# Mtx6BR.net
KiCad netlist of a schematic drawn in EAGLE
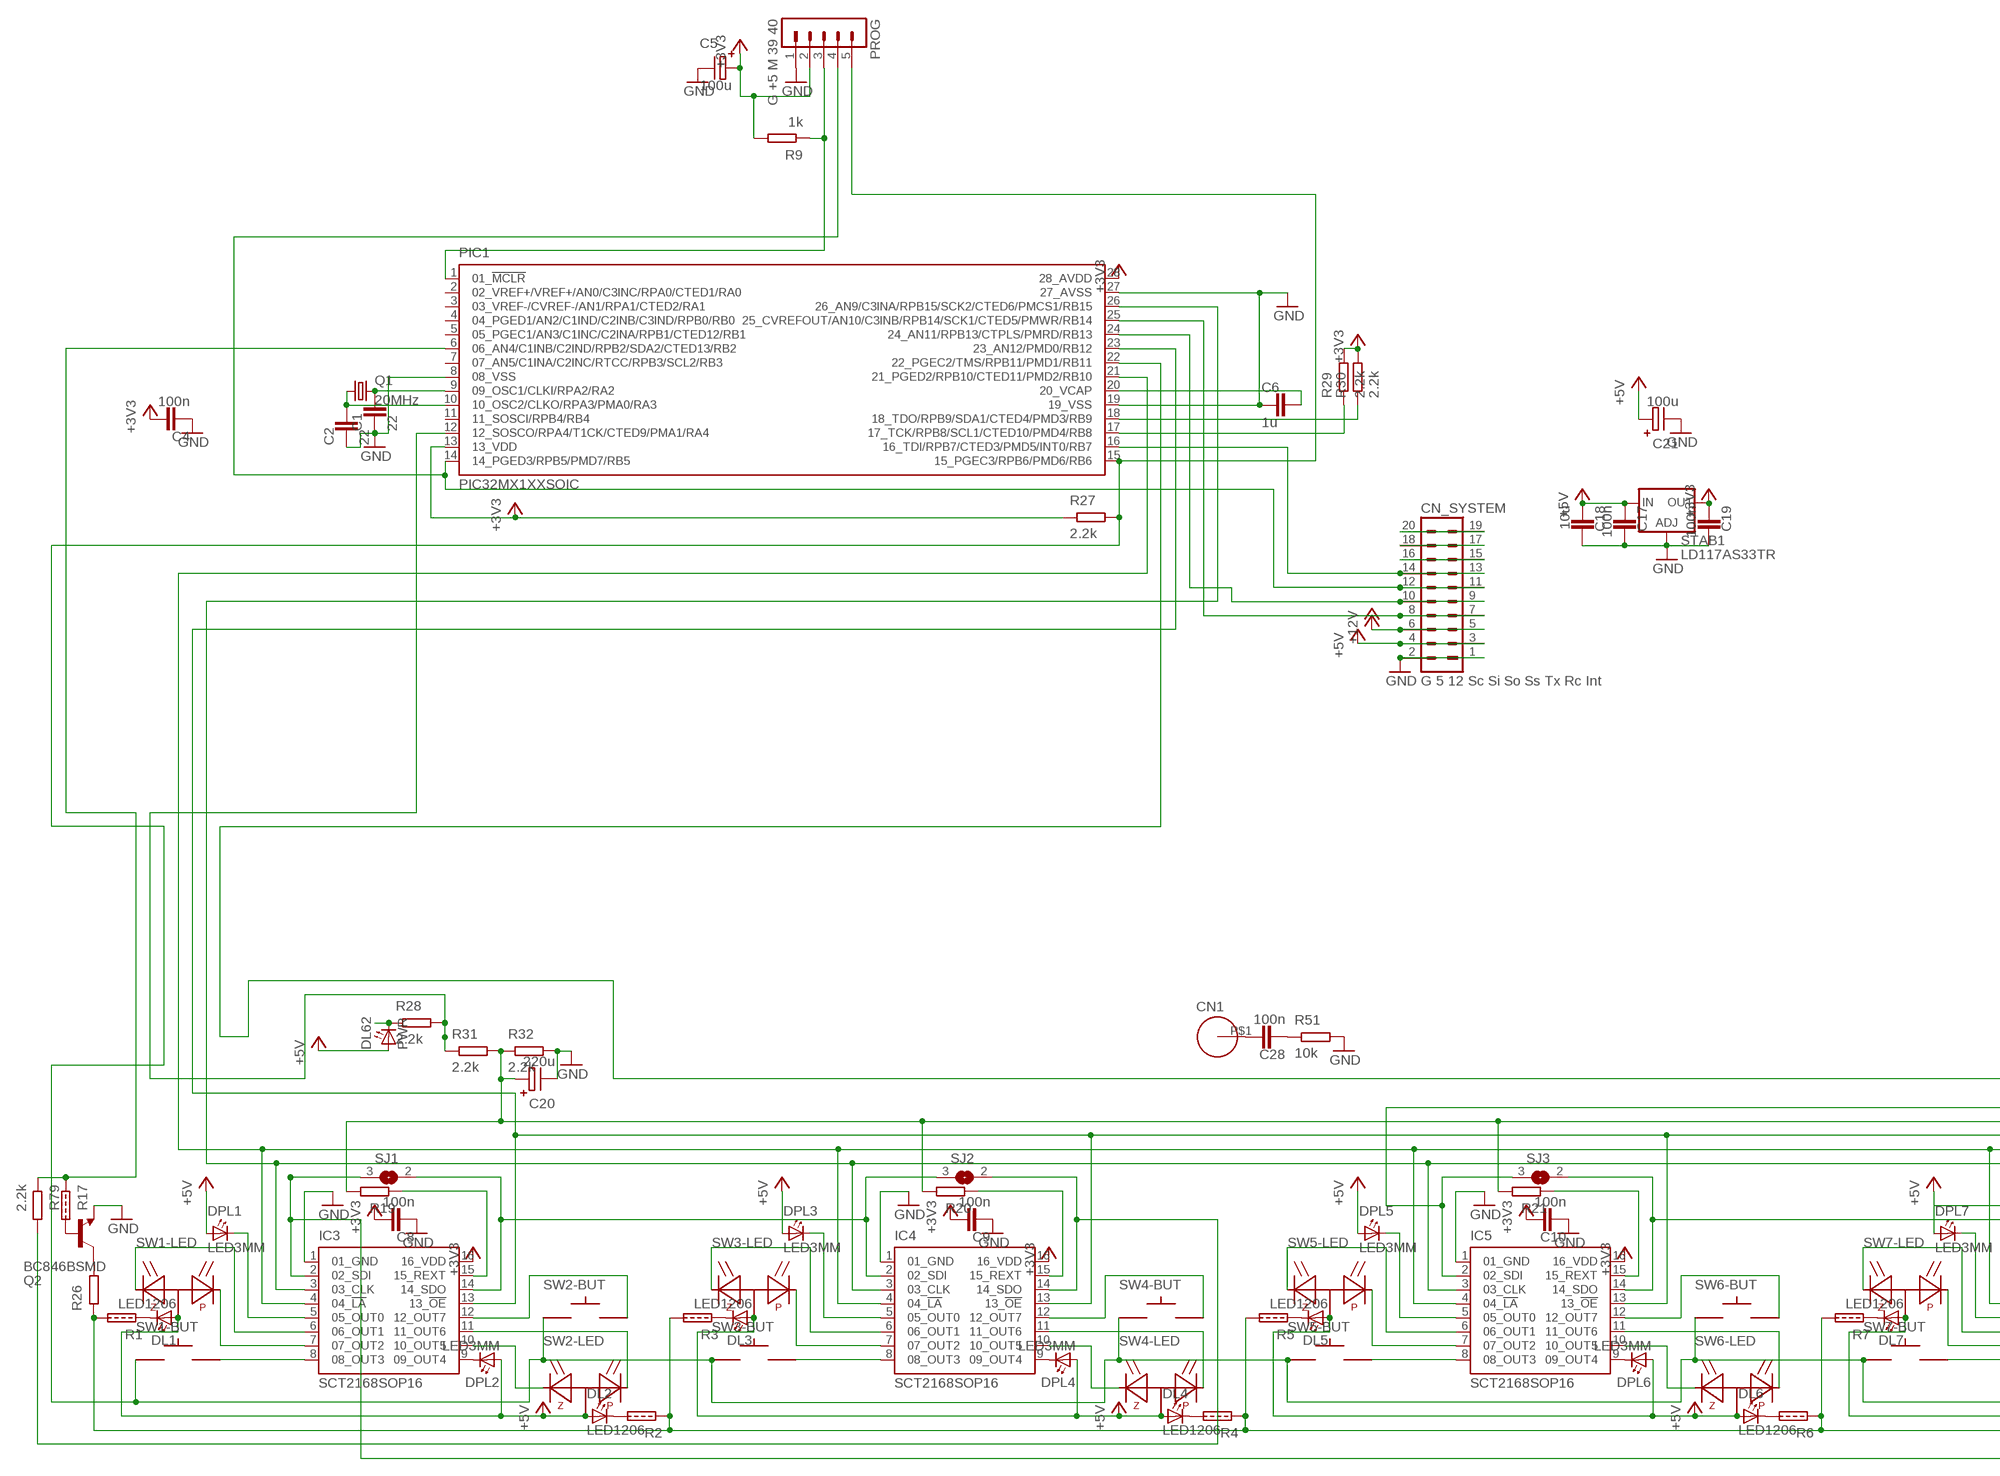
[diagram p0: schematic, sheet 1, part 1 of 2]
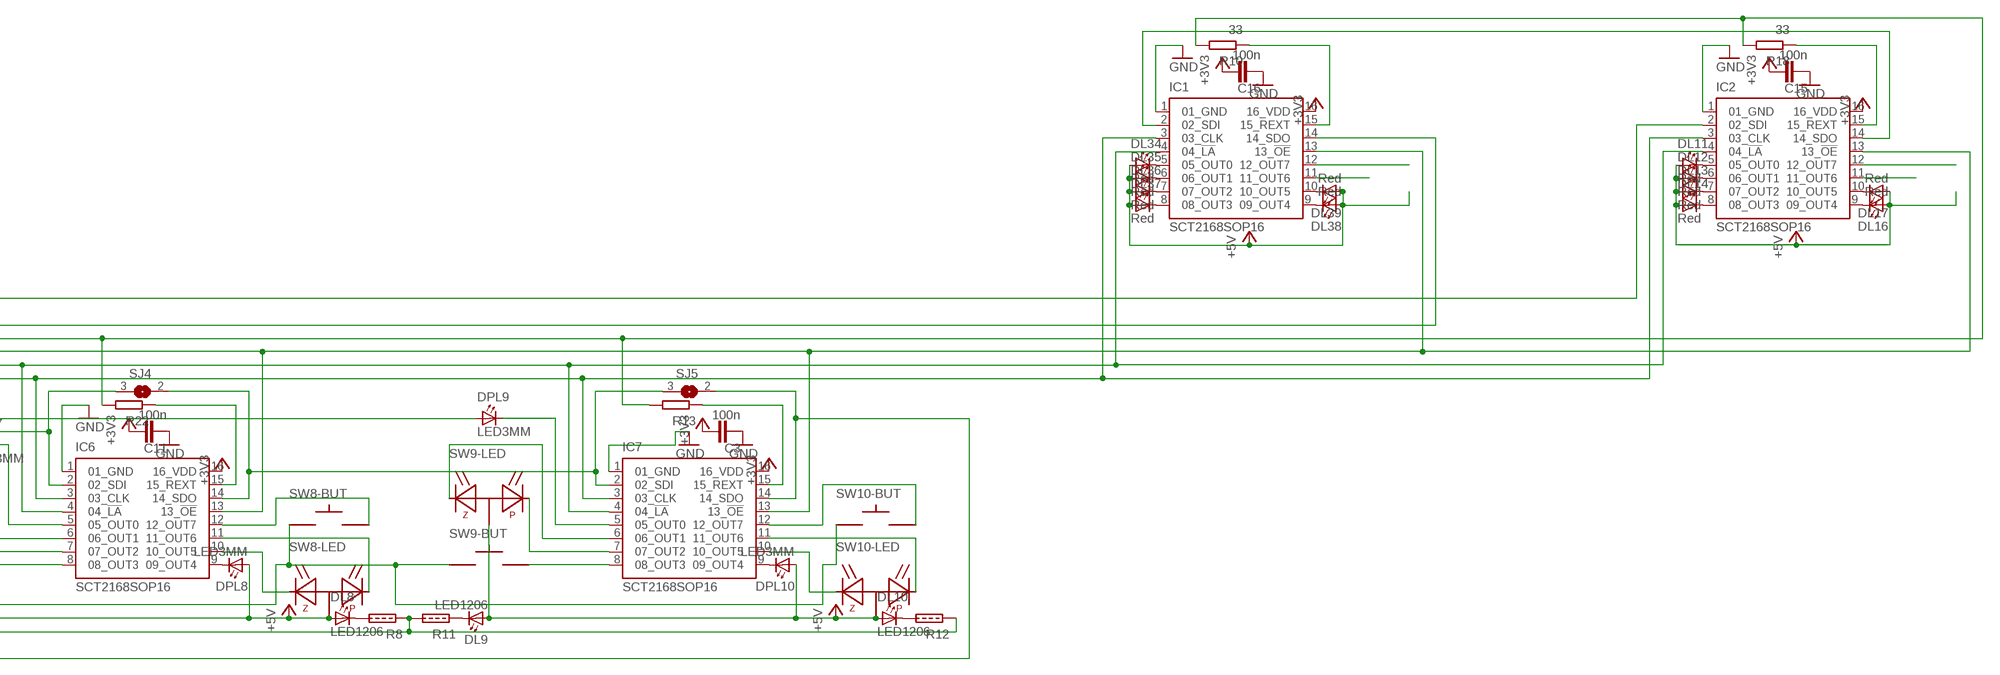
[diagram p1: schematic, sheet 1, part 2 of 2]

(export (version "E")
  (design (tool "Eeschema 10.0.6"))
  (components
    (comp (ref "C1")
      (value "22")
      (footprint "eagle-import:R0805")
      (libsource (lib "eagle-import") (part "C0805"))
    )
    (comp (ref "C2")
      (value "22")
      (footprint "eagle-import:R0805")
      (libsource (lib "eagle-import") (part "C0805"))
    )
    (comp (ref "C3")
      (value "100n")
      (footprint "eagle-import:R0805")
      (libsource (lib "eagle-import") (part "C0805"))
    )
    (comp (ref "C4")
      (value "100n")
      (footprint "eagle-import:R0805")
      (libsource (lib "eagle-import") (part "C0805"))
    )
    (comp (ref "C5")
      (value "100u")
      (footprint "eagle-import:C_EL1RASZT07")
      (libsource (lib "eagle-import") (part "C_EL1R07"))
    )
    (comp (ref "C6")
      (value "1u")
      (footprint "eagle-import:R0805")
      (libsource (lib "eagle-import") (part "C0805"))
    )
    (comp (ref "C8")
      (value "100n")
      (footprint "eagle-import:R0805")
      (libsource (lib "eagle-import") (part "C0805"))
    )
    (comp (ref "C9")
      (value "100n")
      (footprint "eagle-import:R0805")
      (libsource (lib "eagle-import") (part "C0805"))
    )
    (comp (ref "C10")
      (value "100n")
      (footprint "eagle-import:R0805")
      (libsource (lib "eagle-import") (part "C0805"))
    )
    (comp (ref "C11")
      (value "100n")
      (footprint "eagle-import:R0805")
      (libsource (lib "eagle-import") (part "C0805"))
    )
    (comp (ref "C15")
      (value "100n")
      (footprint "eagle-import:R0805")
      (libsource (lib "eagle-import") (part "C0805"))
    )
    (comp (ref "C16")
      (value "100n")
      (footprint "eagle-import:R0805")
      (libsource (lib "eagle-import") (part "C0805"))
    )
    (comp (ref "C17")
      (value "100n")
      (footprint "eagle-import:R0805")
      (libsource (lib "eagle-import") (part "C0805"))
    )
    (comp (ref "C18")
      (value "10u")
      (footprint "eagle-import:R0805")
      (libsource (lib "eagle-import") (part "C0805"))
    )
    (comp (ref "C19")
      (value "100n")
      (footprint "eagle-import:R0805")
      (libsource (lib "eagle-import") (part "C0805"))
    )
    (comp (ref "C20")
      (value "220u")
      (footprint "eagle-import:C_EL1RASZT07")
      (libsource (lib "eagle-import") (part "C_EL1R07"))
    )
    (comp (ref "C21")
      (value "100u")
      (footprint "eagle-import:C_EL1RASZT07")
      (libsource (lib "eagle-import") (part "C_EL1R07"))
    )
    (comp (ref "C28")
      (value "100n")
      (footprint "eagle-import:R0805")
      (libsource (lib "eagle-import") (part "C0805"))
    )
    (comp (ref "CN1")
      (value "TESTCSAVAR3.5")
      (footprint "eagle-import:TESTCSAVAR_3.5")
      (libsource (lib "eagle-import") (part "TESTCSAVAR3.5"))
    )
    (comp (ref "CN_SYSTEM")
      (value "G 5 12 Sc Si So Ss Tx Rc Int")
      (footprint "eagle-import:PIN10_2")
      (libsource (lib "eagle-import") (part "PIN10_2"))
    )
    (comp (ref "DL1")
      (value "LED1206")
      (footprint "eagle-import:R1206")
      (libsource (lib "eagle-import") (part "LED1206"))
    )
    (comp (ref "DL2")
      (value "LED1206")
      (footprint "eagle-import:R1206")
      (libsource (lib "eagle-import") (part "LED1206"))
    )
    (comp (ref "DL3")
      (value "LED1206")
      (footprint "eagle-import:R1206")
      (libsource (lib "eagle-import") (part "LED1206"))
    )
    (comp (ref "DL4")
      (value "LED1206")
      (footprint "eagle-import:R1206")
      (libsource (lib "eagle-import") (part "LED1206"))
    )
    (comp (ref "DL5")
      (value "LED1206")
      (footprint "eagle-import:R1206")
      (libsource (lib "eagle-import") (part "LED1206"))
    )
    (comp (ref "DL6")
      (value "LED1206")
      (footprint "eagle-import:R1206")
      (libsource (lib "eagle-import") (part "LED1206"))
    )
    (comp (ref "DL7")
      (value "LED1206")
      (footprint "eagle-import:R1206")
      (libsource (lib "eagle-import") (part "LED1206"))
    )
    (comp (ref "DL8")
      (value "LED1206")
      (footprint "eagle-import:R1206")
      (libsource (lib "eagle-import") (part "LED1206"))
    )
    (comp (ref "DL9")
      (value "LED1206")
      (footprint "eagle-import:R1206")
      (libsource (lib "eagle-import") (part "LED1206"))
    )
    (comp (ref "DL10")
      (value "LED1206")
      (footprint "eagle-import:R1206")
      (libsource (lib "eagle-import") (part "LED1206"))
    )
    (comp (ref "DL11")
      (value "Red")
      (footprint "eagle-import:LED5MM")
      (libsource (lib "eagle-import") (part "LED5MM"))
    )
    (comp (ref "DL12")
      (value "Red")
      (footprint "eagle-import:LED5MM")
      (libsource (lib "eagle-import") (part "LED5MM"))
    )
    (comp (ref "DL13")
      (value "Red")
      (footprint "eagle-import:LED5MM")
      (libsource (lib "eagle-import") (part "LED5MM"))
    )
    (comp (ref "DL14")
      (value "Red")
      (footprint "eagle-import:LED5MM")
      (libsource (lib "eagle-import") (part "LED5MM"))
    )
    (comp (ref "DL16")
      (value "Red")
      (footprint "eagle-import:LED5MM")
      (libsource (lib "eagle-import") (part "LED5MM"))
    )
    (comp (ref "DL17")
      (value "Red")
      (footprint "eagle-import:LED5MM")
      (libsource (lib "eagle-import") (part "LED5MM"))
    )
    (comp (ref "DL34")
      (value "Red")
      (footprint "eagle-import:LED5MM")
      (libsource (lib "eagle-import") (part "LED5MM"))
    )
    (comp (ref "DL35")
      (value "Red")
      (footprint "eagle-import:LED5MM")
      (libsource (lib "eagle-import") (part "LED5MM"))
    )
    (comp (ref "DL36")
      (value "Red")
      (footprint "eagle-import:LED5MM")
      (libsource (lib "eagle-import") (part "LED5MM"))
    )
    (comp (ref "DL37")
      (value "Red")
      (footprint "eagle-import:LED5MM")
      (libsource (lib "eagle-import") (part "LED5MM"))
    )
    (comp (ref "DL38")
      (value "Red")
      (footprint "eagle-import:LED5MM")
      (libsource (lib "eagle-import") (part "LED5MM"))
    )
    (comp (ref "DL39")
      (value "Red")
      (footprint "eagle-import:LED5MM")
      (libsource (lib "eagle-import") (part "LED5MM"))
    )
    (comp (ref "DL62")
      (value "PWR")
      (footprint "eagle-import:LED5MM")
      (libsource (lib "eagle-import") (part "LED5MM"))
    )
    (comp (ref "DPL1")
      (value "LED3MM")
      (footprint "eagle-import:LED3MM")
      (libsource (lib "eagle-import") (part "LED3MM"))
    )
    (comp (ref "DPL2")
      (value "LED3MM")
      (footprint "eagle-import:LED3MM")
      (libsource (lib "eagle-import") (part "LED3MM"))
    )
    (comp (ref "DPL3")
      (value "LED3MM")
      (footprint "eagle-import:LED3MM")
      (libsource (lib "eagle-import") (part "LED3MM"))
    )
    (comp (ref "DPL4")
      (value "LED3MM")
      (footprint "eagle-import:LED3MM")
      (libsource (lib "eagle-import") (part "LED3MM"))
    )
    (comp (ref "DPL5")
      (value "LED3MM")
      (footprint "eagle-import:LED3MM")
      (libsource (lib "eagle-import") (part "LED3MM"))
    )
    (comp (ref "DPL6")
      (value "LED3MM")
      (footprint "eagle-import:LED3MM")
      (libsource (lib "eagle-import") (part "LED3MM"))
    )
    (comp (ref "DPL7")
      (value "LED3MM")
      (footprint "eagle-import:LED3MM")
      (libsource (lib "eagle-import") (part "LED3MM"))
    )
    (comp (ref "DPL8")
      (value "LED3MM")
      (footprint "eagle-import:LED3MM")
      (libsource (lib "eagle-import") (part "LED3MM"))
    )
    (comp (ref "DPL9")
      (value "LED3MM")
      (footprint "eagle-import:LED3MM")
      (libsource (lib "eagle-import") (part "LED3MM"))
    )
    (comp (ref "DPL10")
      (value "LED3MM")
      (footprint "eagle-import:LED3MM")
      (libsource (lib "eagle-import") (part "LED3MM"))
    )
    (comp (ref "IC1")
      (value "SCT2168SOP16")
      (footprint "eagle-import:SO16")
      (libsource (lib "eagle-import") (part "SCT2168SOP16"))
    )
    (comp (ref "IC2")
      (value "SCT2168SOP16")
      (footprint "eagle-import:SO16")
      (libsource (lib "eagle-import") (part "SCT2168SOP16"))
    )
    (comp (ref "IC3")
      (value "SCT2168SOP16")
      (footprint "eagle-import:SO16")
      (libsource (lib "eagle-import") (part "SCT2168SOP16"))
    )
    (comp (ref "IC4")
      (value "SCT2168SOP16")
      (footprint "eagle-import:SO16")
      (libsource (lib "eagle-import") (part "SCT2168SOP16"))
    )
    (comp (ref "IC5")
      (value "SCT2168SOP16")
      (footprint "eagle-import:SO16")
      (libsource (lib "eagle-import") (part "SCT2168SOP16"))
    )
    (comp (ref "IC6")
      (value "SCT2168SOP16")
      (footprint "eagle-import:SO16")
      (libsource (lib "eagle-import") (part "SCT2168SOP16"))
    )
    (comp (ref "IC7")
      (value "SCT2168SOP16")
      (footprint "eagle-import:SO16")
      (libsource (lib "eagle-import") (part "SCT2168SOP16"))
    )
    (comp (ref "PIC1")
      (value "PIC32MX1XXSOIC")
      (footprint "eagle-import:SOIC127P1032X265-28N")
      (libsource (lib "eagle-import") (part "PIC32MX1XXSOIC"))
    )
    (comp (ref "PROG")
      (value "G +5 M 39 40")
      (footprint "eagle-import:PIN05_1")
      (libsource (lib "eagle-import") (part "PIN05_1"))
    )
    (comp (ref "Q1")
      (value "20MHz")
      (footprint "eagle-import:XTAL_NAGYSMD")
      (libsource (lib "eagle-import") (part "XTAL_2NAGYSMD"))
    )
    (comp (ref "Q2")
      (value "BC846BSMD")
      (footprint "eagle-import:SOT23")
      (libsource (lib "eagle-import") (part "BC846SMDB"))
    )
    (comp (ref "R1")
      (value "RNULL_EU0805")
      (footprint "eagle-import:R0805_C")
      (libsource (lib "eagle-import") (part "RNULL_EU0805"))
    )
    (comp (ref "R2")
      (value "RNULL_EU0805")
      (footprint "eagle-import:R0805_C")
      (libsource (lib "eagle-import") (part "RNULL_EU0805"))
    )
    (comp (ref "R3")
      (value "RNULL_EU0805")
      (footprint "eagle-import:R0805_C")
      (libsource (lib "eagle-import") (part "RNULL_EU0805"))
    )
    (comp (ref "R4")
      (value "RNULL_EU0805")
      (footprint "eagle-import:R0805_C")
      (libsource (lib "eagle-import") (part "RNULL_EU0805"))
    )
    (comp (ref "R5")
      (value "RNULL_EU0805")
      (footprint "eagle-import:R0805_C")
      (libsource (lib "eagle-import") (part "RNULL_EU0805"))
    )
    (comp (ref "R6")
      (value "RNULL_EU0805")
      (footprint "eagle-import:R0805_C")
      (libsource (lib "eagle-import") (part "RNULL_EU0805"))
    )
    (comp (ref "R7")
      (value "RNULL_EU0805")
      (footprint "eagle-import:R0805_C")
      (libsource (lib "eagle-import") (part "RNULL_EU0805"))
    )
    (comp (ref "R8")
      (value "RNULL_EU0805")
      (footprint "eagle-import:R0805_C")
      (libsource (lib "eagle-import") (part "RNULL_EU0805"))
    )
    (comp (ref "R9")
      (value "1k")
      (footprint "eagle-import:R0805")
      (libsource (lib "eagle-import") (part "R_EU0805"))
    )
    (comp (ref "R10")
      (value "33")
      (footprint "eagle-import:R0805")
      (libsource (lib "eagle-import") (part "R_EU0805"))
    )
    (comp (ref "R11")
      (value "RNULL_EU0805")
      (footprint "eagle-import:R0805_C")
      (libsource (lib "eagle-import") (part "RNULL_EU0805"))
    )
    (comp (ref "R12")
      (value "RNULL_EU0805")
      (footprint "eagle-import:R0805_C")
      (libsource (lib "eagle-import") (part "RNULL_EU0805"))
    )
    (comp (ref "R13")
      (value "R_EU0805")
      (footprint "eagle-import:R0805")
      (libsource (lib "eagle-import") (part "R_EU0805"))
    )
    (comp (ref "R17")
      (value "RNULL_EU0805")
      (footprint "eagle-import:R0805_C")
      (libsource (lib "eagle-import") (part "RNULL_EU0805"))
    )
    (comp (ref "R18")
      (value "33")
      (footprint "eagle-import:R0805")
      (libsource (lib "eagle-import") (part "R_EU0805"))
    )
    (comp (ref "R19")
      (value "R_EU0805")
      (footprint "eagle-import:R0805")
      (libsource (lib "eagle-import") (part "R_EU0805"))
    )
    (comp (ref "R20")
      (value "R_EU0805")
      (footprint "eagle-import:R0805")
      (libsource (lib "eagle-import") (part "R_EU0805"))
    )
    (comp (ref "R21")
      (value "R_EU0805")
      (footprint "eagle-import:R0805")
      (libsource (lib "eagle-import") (part "R_EU0805"))
    )
    (comp (ref "R22")
      (value "R_EU0805")
      (footprint "eagle-import:R0805")
      (libsource (lib "eagle-import") (part "R_EU0805"))
    )
    (comp (ref "R26")
      (value "R_EU0805")
      (footprint "eagle-import:R0805")
      (libsource (lib "eagle-import") (part "R_EU0805"))
    )
    (comp (ref "R27")
      (value "2.2k")
      (footprint "eagle-import:R0805")
      (libsource (lib "eagle-import") (part "R_EU0805"))
    )
    (comp (ref "R28")
      (value "2.2k")
      (footprint "eagle-import:R0805")
      (libsource (lib "eagle-import") (part "R_EU0805"))
    )
    (comp (ref "R29")
      (value "2.2k")
      (footprint "eagle-import:R0805")
      (libsource (lib "eagle-import") (part "R_EU0805"))
    )
    (comp (ref "R30")
      (value "2.2k")
      (footprint "eagle-import:R0805")
      (libsource (lib "eagle-import") (part "R_EU0805"))
    )
    (comp (ref "R31")
      (value "2.2k")
      (footprint "eagle-import:R0805")
      (libsource (lib "eagle-import") (part "R_EU0805"))
    )
    (comp (ref "R32")
      (value "2.2k")
      (footprint "eagle-import:R0805")
      (libsource (lib "eagle-import") (part "R_EU0805"))
    )
    (comp (ref "R51")
      (value "10k")
      (footprint "eagle-import:R0805")
      (libsource (lib "eagle-import") (part "R_EU0805"))
    )
    (comp (ref "R79")
      (value "2.2k")
      (footprint "eagle-import:R0805")
      (libsource (lib "eagle-import") (part "R_EU0805"))
    )
    (comp (ref "SJ1") (value "SJ") (footprint "eagle-import:SJ") (libsource (lib "eagle-import") (part "SJ")))
    (comp (ref "SJ2") (value "SJ") (footprint "eagle-import:SJ") (libsource (lib "eagle-import") (part "SJ")))
    (comp (ref "SJ3") (value "SJ") (footprint "eagle-import:SJ") (libsource (lib "eagle-import") (part "SJ")))
    (comp (ref "SJ4") (value "SJ") (footprint "eagle-import:SJ") (libsource (lib "eagle-import") (part "SJ")))
    (comp (ref "SJ5") (value "SJ") (footprint "eagle-import:SJ") (libsource (lib "eagle-import") (part "SJ")))
    (comp (ref "STAB1")
      (value "LD117AS33TR")
      (footprint "eagle-import:SOT223")
      (libsource (lib "eagle-import") (part "LD117A?S33TR"))
    )
    (comp (ref "SW1")
      (value "SPG2")
      (footprint "eagle-import:SPG2_3LED")
      (libsource (lib "eagle-import") (part "SPG2"))
    )
    (comp (ref "SW2")
      (value "SPG2")
      (footprint "eagle-import:SPG2_3LED")
      (libsource (lib "eagle-import") (part "SPG2"))
    )
    (comp (ref "SW3")
      (value "SPG2")
      (footprint "eagle-import:SPG2_3LED")
      (libsource (lib "eagle-import") (part "SPG2"))
    )
    (comp (ref "SW4")
      (value "SPG2")
      (footprint "eagle-import:SPG2_3LED")
      (libsource (lib "eagle-import") (part "SPG2"))
    )
    (comp (ref "SW5")
      (value "SPG2")
      (footprint "eagle-import:SPG2_3LED")
      (libsource (lib "eagle-import") (part "SPG2"))
    )
    (comp (ref "SW6")
      (value "SPG2")
      (footprint "eagle-import:SPG2_3LED")
      (libsource (lib "eagle-import") (part "SPG2"))
    )
    (comp (ref "SW7")
      (value "SPG2")
      (footprint "eagle-import:SPG2_3LED")
      (libsource (lib "eagle-import") (part "SPG2"))
    )
    (comp (ref "SW8")
      (value "SPG2")
      (footprint "eagle-import:SPG2_3LED")
      (libsource (lib "eagle-import") (part "SPG2"))
    )
    (comp (ref "SW9")
      (value "SPG2")
      (footprint "eagle-import:SPG2_3LED")
      (libsource (lib "eagle-import") (part "SPG2"))
    )
    (comp (ref "SW10")
      (value "SPG2")
      (footprint "eagle-import:SPG2_3LED")
      (libsource (lib "eagle-import") (part "SPG2"))
    )
  )
  (nets
    (net (code "1") (name "+3V3") (class "Default")
      (node (ref "C10") (pin "1") (pinfunction "1_1") (pintype "passive"))
      (node (ref "C11") (pin "1") (pinfunction "1_1") (pintype "passive"))
      (node (ref "C15") (pin "1") (pinfunction "1_1") (pintype "passive"))
      (node (ref "C16") (pin "1") (pinfunction "1_1") (pintype "passive"))
      (node (ref "C19") (pin "2") (pinfunction "2_2") (pintype "passive"))
      (node (ref "C3") (pin "1") (pinfunction "1_1") (pintype "passive"))
      (node (ref "C4") (pin "1") (pinfunction "1_1") (pintype "passive"))
      (node (ref "C5") (pin "P+") (pinfunction "P+_P+") (pintype "passive"))
      (node (ref "C8") (pin "1") (pinfunction "1_1") (pintype "passive"))
      (node (ref "C9") (pin "1") (pinfunction "1_1") (pintype "passive"))
      (node (ref "IC1") (pin "16") (pinfunction "16_VDD_16") (pintype "power_in"))
      (node (ref "IC2") (pin "16") (pinfunction "16_VDD_16") (pintype "power_in"))
      (node (ref "IC3") (pin "16") (pinfunction "16_VDD_16") (pintype "power_in"))
      (node (ref "IC4") (pin "16") (pinfunction "16_VDD_16") (pintype "power_in"))
      (node (ref "IC5") (pin "16") (pinfunction "16_VDD_16") (pintype "power_in"))
      (node (ref "IC6") (pin "16") (pinfunction "16_VDD_16") (pintype "power_in"))
      (node (ref "IC7") (pin "16") (pinfunction "16_VDD_16") (pintype "power_in"))
      (node (ref "PIC1") (pin "13") (pinfunction "13_VDD_13") (pintype "bidirectional"))
      (node (ref "PIC1") (pin "28") (pinfunction "28_AVDD_28") (pintype "bidirectional"))
      (node (ref "PROG") (pin "2") (pinfunction "2_2") (pintype "passive"))
      (node (ref "R27") (pin "1") (pinfunction "A_1") (pintype "passive"))
      (node (ref "R29") (pin "2") (pinfunction "E_2") (pintype "passive"))
      (node (ref "R30") (pin "2") (pinfunction "E_2") (pintype "passive"))
      (node (ref "R9") (pin "2") (pinfunction "E_2") (pintype "passive"))
      (node (ref "STAB1") (pin "4") (pinfunction "OUT_4") (pintype "passive"))
    )
    (net (code "2") (name "+5V") (class "Default")
      (node (ref "C17") (pin "2") (pinfunction "2_2") (pintype "passive"))
      (node (ref "C18") (pin "2") (pinfunction "2_2") (pintype "passive"))
      (node (ref "C21") (pin "P+") (pinfunction "P+_P+") (pintype "passive"))
      (node (ref "CN_SYSTEM") (pin "3") (pinfunction "3_3") (pintype "passive"))
      (node (ref "CN_SYSTEM") (pin "4") (pinfunction "4_4") (pintype "passive"))
      (node (ref "DL1") (pin "1") (pinfunction "A_1") (pintype "passive"))
      (node (ref "DL10") (pin "1") (pinfunction "A_1") (pintype "passive"))
      (node (ref "DL11") (pin "A") (pinfunction "A_A") (pintype "passive"))
      (node (ref "DL12") (pin "A") (pinfunction "A_A") (pintype "passive"))
      (node (ref "DL13") (pin "A") (pinfunction "A_A") (pintype "passive"))
      (node (ref "DL14") (pin "A") (pinfunction "A_A") (pintype "passive"))
      (node (ref "DL16") (pin "A") (pinfunction "A_A") (pintype "passive"))
      (node (ref "DL17") (pin "A") (pinfunction "A_A") (pintype "passive"))
      (node (ref "DL2") (pin "1") (pinfunction "A_1") (pintype "passive"))
      (node (ref "DL3") (pin "1") (pinfunction "A_1") (pintype "passive"))
      (node (ref "DL34") (pin "A") (pinfunction "A_A") (pintype "passive"))
      (node (ref "DL35") (pin "A") (pinfunction "A_A") (pintype "passive"))
      (node (ref "DL36") (pin "A") (pinfunction "A_A") (pintype "passive"))
      (node (ref "DL37") (pin "A") (pinfunction "A_A") (pintype "passive"))
      (node (ref "DL38") (pin "A") (pinfunction "A_A") (pintype "passive"))
      (node (ref "DL39") (pin "A") (pinfunction "A_A") (pintype "passive"))
      (node (ref "DL4") (pin "1") (pinfunction "A_1") (pintype "passive"))
      (node (ref "DL5") (pin "1") (pinfunction "A_1") (pintype "passive"))
      (node (ref "DL6") (pin "1") (pinfunction "A_1") (pintype "passive"))
      (node (ref "DL62") (pin "A") (pinfunction "A_A") (pintype "passive"))
      (node (ref "DL7") (pin "1") (pinfunction "A_1") (pintype "passive"))
      (node (ref "DL8") (pin "1") (pinfunction "A_1") (pintype "passive"))
      (node (ref "DL9") (pin "1") (pinfunction "A_1") (pintype "passive"))
      (node (ref "DPL1") (pin "A") (pinfunction "A_A") (pintype "passive"))
      (node (ref "DPL10") (pin "A") (pinfunction "A_A") (pintype "passive"))
      (node (ref "DPL2") (pin "A") (pinfunction "A_A") (pintype "passive"))
      (node (ref "DPL3") (pin "A") (pinfunction "A_A") (pintype "passive"))
      (node (ref "DPL4") (pin "A") (pinfunction "A_A") (pintype "passive"))
      (node (ref "DPL5") (pin "A") (pinfunction "A_A") (pintype "passive"))
      (node (ref "DPL6") (pin "A") (pinfunction "A_A") (pintype "passive"))
      (node (ref "DPL7") (pin "A") (pinfunction "A_A") (pintype "passive"))
      (node (ref "DPL8") (pin "A") (pinfunction "A_A") (pintype "passive"))
      (node (ref "DPL9") (pin "A") (pinfunction "A_A") (pintype "passive"))
      (node (ref "STAB1") (pin "3") (pinfunction "IN_3") (pintype "input"))
      (node (ref "SW1") (pin "LED+") (pinfunction "+_LED+") (pintype "bidirectional"))
      (node (ref "SW10") (pin "LED+") (pinfunction "+_LED+") (pintype "bidirectional"))
      (node (ref "SW2") (pin "LED+") (pinfunction "+_LED+") (pintype "bidirectional"))
      (node (ref "SW3") (pin "LED+") (pinfunction "+_LED+") (pintype "bidirectional"))
      (node (ref "SW4") (pin "LED+") (pinfunction "+_LED+") (pintype "bidirectional"))
      (node (ref "SW5") (pin "LED+") (pinfunction "+_LED+") (pintype "bidirectional"))
      (node (ref "SW6") (pin "LED+") (pinfunction "+_LED+") (pintype "bidirectional"))
      (node (ref "SW7") (pin "LED+") (pinfunction "+_LED+") (pintype "bidirectional"))
      (node (ref "SW8") (pin "LED+") (pinfunction "+_LED+") (pintype "bidirectional"))
      (node (ref "SW9") (pin "LED+") (pinfunction "+_LED+") (pintype "bidirectional"))
    )
    (net (code "3") (name "+12V") (class "Default")
      (node (ref "CN_SYSTEM") (pin "5") (pinfunction "5_5") (pintype "passive"))
      (node (ref "CN_SYSTEM") (pin "6") (pinfunction "6_6") (pintype "passive"))
    )
    (net (code "4") (name "GND") (class "Default")
      (node (ref "C1") (pin "2") (pinfunction "2_2") (pintype "passive"))
      (node (ref "C10") (pin "2") (pinfunction "2_2") (pintype "passive"))
      (node (ref "C11") (pin "2") (pinfunction "2_2") (pintype "passive"))
      (node (ref "C15") (pin "2") (pinfunction "2_2") (pintype "passive"))
      (node (ref "C16") (pin "2") (pinfunction "2_2") (pintype "passive"))
      (node (ref "C17") (pin "1") (pinfunction "1_1") (pintype "passive"))
      (node (ref "C18") (pin "1") (pinfunction "1_1") (pintype "passive"))
      (node (ref "C19") (pin "1") (pinfunction "1_1") (pintype "passive"))
      (node (ref "C2") (pin "2") (pinfunction "2_2") (pintype "passive"))
      (node (ref "C20") (pin "P-") (pinfunction "P-_P-") (pintype "passive"))
      (node (ref "C21") (pin "P-") (pinfunction "P-_P-") (pintype "passive"))
      (node (ref "C3") (pin "2") (pinfunction "2_2") (pintype "passive"))
      (node (ref "C4") (pin "2") (pinfunction "2_2") (pintype "passive"))
      (node (ref "C5") (pin "P-") (pinfunction "P-_P-") (pintype "passive"))
      (node (ref "C6") (pin "2") (pinfunction "2_2") (pintype "passive"))
      (node (ref "C8") (pin "2") (pinfunction "2_2") (pintype "passive"))
      (node (ref "C9") (pin "2") (pinfunction "2_2") (pintype "passive"))
      (node (ref "CN_SYSTEM") (pin "1") (pinfunction "1_1") (pintype "passive"))
      (node (ref "CN_SYSTEM") (pin "2") (pinfunction "2_2") (pintype "passive"))
      (node (ref "IC1") (pin "1") (pinfunction "01_GND_1") (pintype "power_in"))
      (node (ref "IC2") (pin "1") (pinfunction "01_GND_1") (pintype "power_in"))
      (node (ref "IC3") (pin "1") (pinfunction "01_GND_1") (pintype "power_in"))
      (node (ref "IC4") (pin "1") (pinfunction "01_GND_1") (pintype "power_in"))
      (node (ref "IC5") (pin "1") (pinfunction "01_GND_1") (pintype "power_in"))
      (node (ref "IC6") (pin "1") (pinfunction "01_GND_1") (pintype "power_in"))
      (node (ref "IC7") (pin "1") (pinfunction "01_GND_1") (pintype "power_in"))
      (node (ref "PIC1") (pin "19") (pinfunction "19_VSS_19") (pintype "power_in"))
      (node (ref "PIC1") (pin "27") (pinfunction "27_AVSS_27") (pintype "bidirectional"))
      (node (ref "PIC1") (pin "8") (pinfunction "08_VSS_8") (pintype "power_in"))
      (node (ref "PROG") (pin "1") (pinfunction "1_1") (pintype "passive"))
      (node (ref "Q2") (pin "2") (pinfunction "E_2") (pintype "passive"))
      (node (ref "R32") (pin "2") (pinfunction "E_2") (pintype "passive"))
      (node (ref "R51") (pin "2") (pinfunction "E_2") (pintype "passive"))
      (node (ref "STAB1") (pin "1") (pinfunction "ADJ_1") (pintype "input"))
    )
    (net (code "5") (name "Net-(CN1-1)") (class "Default")
      (node (ref "C28") (pin "1") (pinfunction "1_1") (pintype "passive"))
      (node (ref "CN1") (pin "P$1") (pinfunction "1_P$1") (pintype "passive"))
    )
    (net (code "6") (name "Net-(CN_SYSTEM-Pad15)") (class "Default")
      (node (ref "CN_SYSTEM") (pin "15") (pinfunction "15_15") (pintype "passive"))
      (node (ref "CN_SYSTEM") (pin "16") (pinfunction "16_16") (pintype "passive"))
    )
    (net (code "7") (name "Net-(CN_SYSTEM-Pad17)") (class "Default")
      (node (ref "CN_SYSTEM") (pin "17") (pinfunction "17_17") (pintype "passive"))
      (node (ref "CN_SYSTEM") (pin "18") (pinfunction "18_18") (pintype "passive"))
    )
    (net (code "8") (name "Net-(CN_SYSTEM-Pad19)") (class "Default")
      (node (ref "CN_SYSTEM") (pin "19") (pinfunction "19_19") (pintype "passive"))
      (node (ref "CN_SYSTEM") (pin "20") (pinfunction "20_20") (pintype "passive"))
    )
    (net (code "9") (name "Net-(DL1-C)") (class "Default")
      (node (ref "DL1") (pin "2") (pinfunction "C_2") (pintype "passive"))
      (node (ref "R1") (pin "1") (pinfunction "A_1") (pintype "passive"))
    )
    (net (code "10") (name "Net-(DL2-C)") (class "Default")
      (node (ref "DL2") (pin "2") (pinfunction "C_2") (pintype "passive"))
      (node (ref "R2") (pin "2") (pinfunction "E_2") (pintype "passive"))
    )
    (net (code "11") (name "Net-(DL3-C)") (class "Default")
      (node (ref "DL3") (pin "2") (pinfunction "C_2") (pintype "passive"))
      (node (ref "R3") (pin "1") (pinfunction "A_1") (pintype "passive"))
    )
    (net (code "12") (name "Net-(DL4-C)") (class "Default")
      (node (ref "DL4") (pin "2") (pinfunction "C_2") (pintype "passive"))
      (node (ref "R4") (pin "2") (pinfunction "E_2") (pintype "passive"))
    )
    (net (code "13") (name "Net-(DL5-C)") (class "Default")
      (node (ref "DL5") (pin "2") (pinfunction "C_2") (pintype "passive"))
      (node (ref "R5") (pin "1") (pinfunction "A_1") (pintype "passive"))
    )
    (net (code "14") (name "Net-(DL6-C)") (class "Default")
      (node (ref "DL6") (pin "2") (pinfunction "C_2") (pintype "passive"))
      (node (ref "R6") (pin "2") (pinfunction "E_2") (pintype "passive"))
    )
    (net (code "15") (name "Net-(DL7-C)") (class "Default")
      (node (ref "DL7") (pin "2") (pinfunction "C_2") (pintype "passive"))
      (node (ref "R7") (pin "1") (pinfunction "A_1") (pintype "passive"))
    )
    (net (code "16") (name "Net-(DL8-C)") (class "Default")
      (node (ref "DL8") (pin "2") (pinfunction "C_2") (pintype "passive"))
      (node (ref "R8") (pin "2") (pinfunction "E_2") (pintype "passive"))
    )
    (net (code "17") (name "Net-(DL9-C)") (class "Default")
      (node (ref "DL9") (pin "2") (pinfunction "C_2") (pintype "passive"))
      (node (ref "R11") (pin "1") (pinfunction "A_1") (pintype "passive"))
    )
    (net (code "18") (name "Net-(DL10-C)") (class "Default")
      (node (ref "DL10") (pin "2") (pinfunction "C_2") (pintype "passive"))
      (node (ref "R12") (pin "2") (pinfunction "E_2") (pintype "passive"))
    )
    (net (code "19") (name "Net-(DL11-C)") (class "Default")
      (node (ref "DL11") (pin "K") (pinfunction "C_K") (pintype "passive"))
      (node (ref "IC2") (pin "5") (pinfunction "05_OUT0_5") (pintype "output"))
    )
    (net (code "20") (name "Net-(DL12-C)") (class "Default")
      (node (ref "DL12") (pin "K") (pinfunction "C_K") (pintype "passive"))
      (node (ref "IC2") (pin "6") (pinfunction "06_OUT1_6") (pintype "output"))
    )
    (net (code "21") (name "Net-(DL13-C)") (class "Default")
      (node (ref "DL13") (pin "K") (pinfunction "C_K") (pintype "passive"))
      (node (ref "IC2") (pin "7") (pinfunction "07_OUT2_7") (pintype "output"))
    )
    (net (code "22") (name "Net-(DL14-C)") (class "Default")
      (node (ref "DL14") (pin "K") (pinfunction "C_K") (pintype "passive"))
      (node (ref "IC2") (pin "8") (pinfunction "08_OUT3_8") (pintype "output"))
    )
    (net (code "23") (name "Net-(DL16-C)") (class "Default")
      (node (ref "DL16") (pin "K") (pinfunction "C_K") (pintype "passive"))
      (node (ref "IC2") (pin "9") (pinfunction "09_OUT4_9") (pintype "output"))
    )
    (net (code "24") (name "Net-(DL17-C)") (class "Default")
      (node (ref "DL17") (pin "K") (pinfunction "C_K") (pintype "passive"))
      (node (ref "IC2") (pin "10") (pinfunction "10_OUT5_10") (pintype "output"))
    )
    (net (code "25") (name "Net-(DL34-C)") (class "Default")
      (node (ref "DL34") (pin "K") (pinfunction "C_K") (pintype "passive"))
      (node (ref "IC1") (pin "5") (pinfunction "05_OUT0_5") (pintype "output"))
    )
    (net (code "26") (name "Net-(DL35-C)") (class "Default")
      (node (ref "DL35") (pin "K") (pinfunction "C_K") (pintype "passive"))
      (node (ref "IC1") (pin "6") (pinfunction "06_OUT1_6") (pintype "output"))
    )
    (net (code "27") (name "Net-(DL36-C)") (class "Default")
      (node (ref "DL36") (pin "K") (pinfunction "C_K") (pintype "passive"))
      (node (ref "IC1") (pin "7") (pinfunction "07_OUT2_7") (pintype "output"))
    )
    (net (code "28") (name "Net-(DL37-C)") (class "Default")
      (node (ref "DL37") (pin "K") (pinfunction "C_K") (pintype "passive"))
      (node (ref "IC1") (pin "8") (pinfunction "08_OUT3_8") (pintype "output"))
    )
    (net (code "29") (name "Net-(DL38-C)") (class "Default")
      (node (ref "DL38") (pin "K") (pinfunction "C_K") (pintype "passive"))
      (node (ref "IC1") (pin "9") (pinfunction "09_OUT4_9") (pintype "output"))
    )
    (net (code "30") (name "Net-(DL39-C)") (class "Default")
      (node (ref "DL39") (pin "K") (pinfunction "C_K") (pintype "passive"))
      (node (ref "IC1") (pin "10") (pinfunction "10_OUT5_10") (pintype "output"))
    )
    (net (code "31") (name "Net-(DL62-C)") (class "Default")
      (node (ref "DL62") (pin "K") (pinfunction "C_K") (pintype "passive"))
      (node (ref "R28") (pin "1") (pinfunction "A_1") (pintype "passive"))
    )
    (net (code "32") (name "Net-(DPL1-C)") (class "Default")
      (node (ref "DPL1") (pin "K") (pinfunction "C_K") (pintype "passive"))
      (node (ref "IC3") (pin "5") (pinfunction "05_OUT0_5") (pintype "output"))
    )
    (net (code "33") (name "Net-(DPL2-C)") (class "Default")
      (node (ref "DPL2") (pin "K") (pinfunction "C_K") (pintype "passive"))
      (node (ref "IC3") (pin "9") (pinfunction "09_OUT4_9") (pintype "output"))
    )
    (net (code "34") (name "Net-(DPL3-C)") (class "Default")
      (node (ref "DPL3") (pin "K") (pinfunction "C_K") (pintype "passive"))
      (node (ref "IC4") (pin "5") (pinfunction "05_OUT0_5") (pintype "output"))
    )
    (net (code "35") (name "Net-(DPL4-C)") (class "Default")
      (node (ref "DPL4") (pin "K") (pinfunction "C_K") (pintype "passive"))
      (node (ref "IC4") (pin "9") (pinfunction "09_OUT4_9") (pintype "output"))
    )
    (net (code "36") (name "Net-(DPL5-C)") (class "Default")
      (node (ref "DPL5") (pin "K") (pinfunction "C_K") (pintype "passive"))
      (node (ref "IC5") (pin "5") (pinfunction "05_OUT0_5") (pintype "output"))
    )
    (net (code "37") (name "Net-(DPL6-C)") (class "Default")
      (node (ref "DPL6") (pin "K") (pinfunction "C_K") (pintype "passive"))
      (node (ref "IC5") (pin "9") (pinfunction "09_OUT4_9") (pintype "output"))
    )
    (net (code "38") (name "Net-(DPL7-C)") (class "Default")
      (node (ref "DPL7") (pin "K") (pinfunction "C_K") (pintype "passive"))
      (node (ref "IC6") (pin "5") (pinfunction "05_OUT0_5") (pintype "output"))
    )
    (net (code "39") (name "Net-(DPL8-C)") (class "Default")
      (node (ref "DPL8") (pin "K") (pinfunction "C_K") (pintype "passive"))
      (node (ref "IC6") (pin "9") (pinfunction "09_OUT4_9") (pintype "output"))
    )
    (net (code "40") (name "Net-(DPL9-C)") (class "Default")
      (node (ref "DPL9") (pin "K") (pinfunction "C_K") (pintype "passive"))
      (node (ref "IC7") (pin "5") (pinfunction "05_OUT0_5") (pintype "output"))
    )
    (net (code "41") (name "Net-(DPL10-C)") (class "Default")
      (node (ref "DPL10") (pin "K") (pinfunction "C_K") (pintype "passive"))
      (node (ref "IC7") (pin "9") (pinfunction "09_OUT4_9") (pintype "output"))
    )
    (net (code "42") (name "Net-(IC1-02_SDI)") (class "Default")
      (node (ref "IC1") (pin "2") (pinfunction "02_SDI_2") (pintype "input"))
      (node (ref "IC2") (pin "14") (pinfunction "14_SDO_14") (pintype "output"))
    )
    (net (code "43") (name "Net-(IC1-03_CLK)") (class "Default")
      (node (ref "IC1") (pin "3") (pinfunction "03_CLK_3") (pintype "input"))
      (node (ref "IC2") (pin "3") (pinfunction "03_CLK_3") (pintype "input"))
      (node (ref "IC3") (pin "3") (pinfunction "03_CLK_3") (pintype "input"))
      (node (ref "IC4") (pin "3") (pinfunction "03_CLK_3") (pintype "input"))
      (node (ref "IC5") (pin "3") (pinfunction "03_CLK_3") (pintype "input"))
      (node (ref "IC6") (pin "3") (pinfunction "03_CLK_3") (pintype "input"))
      (node (ref "IC7") (pin "3") (pinfunction "03_CLK_3") (pintype "input"))
      (node (ref "PIC1") (pin "26") (pinfunction "26_AN9/C3INA/RPB15/SCK2/CTED6/PMCS1/RB15_26") (pintype "bidirectional"))
    )
    (net (code "44") (name "Net-(IC1-04_~{LA})") (class "Default")
      (node (ref "IC1") (pin "4") (pinfunction "04_~{LA}_4") (pintype "input"))
      (node (ref "IC2") (pin "4") (pinfunction "04_~{LA}_4") (pintype "input"))
      (node (ref "IC3") (pin "4") (pinfunction "04_~{LA}_4") (pintype "input"))
      (node (ref "IC4") (pin "4") (pinfunction "04_~{LA}_4") (pintype "input"))
      (node (ref "IC5") (pin "4") (pinfunction "04_~{LA}_4") (pintype "input"))
      (node (ref "IC6") (pin "4") (pinfunction "04_~{LA}_4") (pintype "input"))
      (node (ref "IC7") (pin "4") (pinfunction "04_~{LA}_4") (pintype "input"))
      (node (ref "PIC1") (pin "21") (pinfunction "21_PGED2/RPB10/CTED11/PMD2/RB10_21") (pintype "bidirectional"))
    )
    (net (code "45") (name "Net-(IC1-13_~{OE})") (class "Default")
      (node (ref "IC1") (pin "13") (pinfunction "13_~{OE}_13") (pintype "input"))
      (node (ref "IC2") (pin "13") (pinfunction "13_~{OE}_13") (pintype "input"))
      (node (ref "IC3") (pin "13") (pinfunction "13_~{OE}_13") (pintype "input"))
      (node (ref "IC4") (pin "13") (pinfunction "13_~{OE}_13") (pintype "input"))
      (node (ref "IC5") (pin "13") (pinfunction "13_~{OE}_13") (pintype "input"))
      (node (ref "IC6") (pin "13") (pinfunction "13_~{OE}_13") (pintype "input"))
      (node (ref "IC7") (pin "13") (pinfunction "13_~{OE}_13") (pintype "input"))
      (node (ref "PIC1") (pin "23") (pinfunction "23_AN12/PMD0/RB12_23") (pintype "bidirectional"))
    )
    (net (code "46") (name "Net-(IC1-14_SDO)") (class "Default")
      (node (ref "IC1") (pin "14") (pinfunction "14_SDO_14") (pintype "output"))
      (node (ref "IC5") (pin "2") (pinfunction "02_SDI_2") (pintype "input"))
      (node (ref "SJ3") (pin "3") (pinfunction "1_3") (pintype "passive"))
    )
    (net (code "47") (name "Net-(IC1-15_REXT)") (class "Default")
      (node (ref "IC1") (pin "15") (pinfunction "15_REXT_15") (pintype "bidirectional"))
      (node (ref "R10") (pin "1") (pinfunction "A_1") (pintype "passive"))
    )
    (net (code "48") (name "Net-(IC2-02_SDI)") (class "Default")
      (node (ref "IC2") (pin "2") (pinfunction "02_SDI_2") (pintype "input"))
      (node (ref "PIC1") (pin "22") (pinfunction "22_PGEC2/TMS/RPB11/PMD1/RB11_22") (pintype "bidirectional"))
    )
    (net (code "49") (name "Net-(IC2-15_REXT)") (class "Default")
      (node (ref "IC2") (pin "15") (pinfunction "15_REXT_15") (pintype "bidirectional"))
      (node (ref "R18") (pin "1") (pinfunction "A_1") (pintype "passive"))
    )
    (net (code "50") (name "Net-(IC3-02_SDI)") (class "Default")
      (node (ref "IC3") (pin "2") (pinfunction "02_SDI_2") (pintype "input"))
      (node (ref "IC7") (pin "14") (pinfunction "14_SDO_14") (pintype "output"))
      (node (ref "SJ1") (pin "3") (pinfunction "1_3") (pintype "passive"))
      (node (ref "SJ5") (pin "2") (pinfunction "2_2") (pintype "passive"))
    )
    (net (code "51") (name "Net-(IC3-06_OUT1)") (class "Default")
      (node (ref "IC3") (pin "6") (pinfunction "06_OUT1_6") (pintype "output"))
      (node (ref "SW1") (pin "Z-") (pinfunction "Z_Z-") (pintype "bidirectional"))
    )
    (net (code "52") (name "Net-(IC3-07_OUT2)") (class "Default")
      (node (ref "IC3") (pin "7") (pinfunction "07_OUT2_7") (pintype "output"))
      (node (ref "SW1") (pin "P-") (pinfunction "P_P-") (pintype "bidirectional"))
    )
    (net (code "53") (name "Net-(IC3-08_OUT3)") (class "Default")
      (node (ref "IC3") (pin "8") (pinfunction "08_OUT3_8") (pintype "output"))
      (node (ref "SW1") (pin "G2") (pinfunction "G2_G2") (pintype "bidirectional"))
    )
    (net (code "54") (name "Net-(IC3-10_OUT5)") (class "Default")
      (node (ref "IC3") (pin "10") (pinfunction "10_OUT5_10") (pintype "output"))
      (node (ref "SW2") (pin "Z-") (pinfunction "Z_Z-") (pintype "bidirectional"))
    )
    (net (code "55") (name "Net-(IC3-11_OUT6)") (class "Default")
      (node (ref "IC3") (pin "11") (pinfunction "11_OUT6_11") (pintype "output"))
      (node (ref "SW2") (pin "P-") (pinfunction "P_P-") (pintype "bidirectional"))
    )
    (net (code "56") (name "Net-(IC3-12_OUT7)") (class "Default")
      (node (ref "IC3") (pin "12") (pinfunction "12_OUT7_12") (pintype "output"))
      (node (ref "SW2") (pin "G2") (pinfunction "G2_G2") (pintype "bidirectional"))
    )
    (net (code "57") (name "Net-(IC3-14_SDO)") (class "Default")
      (node (ref "IC3") (pin "14") (pinfunction "14_SDO_14") (pintype "output"))
      (node (ref "IC4") (pin "2") (pinfunction "02_SDI_2") (pintype "input"))
      (node (ref "SJ1") (pin "2") (pinfunction "2_2") (pintype "passive"))
      (node (ref "SJ2") (pin "3") (pinfunction "1_3") (pintype "passive"))
    )
    (net (code "58") (name "Net-(IC3-15_REXT)") (class "Default")
      (node (ref "IC3") (pin "15") (pinfunction "15_REXT_15") (pintype "bidirectional"))
      (node (ref "R19") (pin "1") (pinfunction "A_1") (pintype "passive"))
    )
    (net (code "59") (name "Net-(IC4-06_OUT1)") (class "Default")
      (node (ref "IC4") (pin "6") (pinfunction "06_OUT1_6") (pintype "output"))
      (node (ref "SW3") (pin "Z-") (pinfunction "Z_Z-") (pintype "bidirectional"))
    )
    (net (code "60") (name "Net-(IC4-07_OUT2)") (class "Default")
      (node (ref "IC4") (pin "7") (pinfunction "07_OUT2_7") (pintype "output"))
      (node (ref "SW3") (pin "P-") (pinfunction "P_P-") (pintype "bidirectional"))
    )
    (net (code "61") (name "Net-(IC4-08_OUT3)") (class "Default")
      (node (ref "IC4") (pin "8") (pinfunction "08_OUT3_8") (pintype "output"))
      (node (ref "SW3") (pin "G2") (pinfunction "G2_G2") (pintype "bidirectional"))
    )
    (net (code "62") (name "Net-(IC4-10_OUT5)") (class "Default")
      (node (ref "IC4") (pin "10") (pinfunction "10_OUT5_10") (pintype "output"))
      (node (ref "SW4") (pin "Z-") (pinfunction "Z_Z-") (pintype "bidirectional"))
    )
    (net (code "63") (name "Net-(IC4-11_OUT6)") (class "Default")
      (node (ref "IC4") (pin "11") (pinfunction "11_OUT6_11") (pintype "output"))
      (node (ref "SW4") (pin "P-") (pinfunction "P_P-") (pintype "bidirectional"))
    )
    (net (code "64") (name "Net-(IC4-12_OUT7)") (class "Default")
      (node (ref "IC4") (pin "12") (pinfunction "12_OUT7_12") (pintype "output"))
      (node (ref "SW4") (pin "G2") (pinfunction "G2_G2") (pintype "bidirectional"))
    )
    (net (code "65") (name "Net-(IC4-14_SDO)") (class "Default")
      (node (ref "IC4") (pin "14") (pinfunction "14_SDO_14") (pintype "output"))
      (node (ref "R79") (pin "2") (pinfunction "E_2") (pintype "passive"))
      (node (ref "SJ2") (pin "2") (pinfunction "2_2") (pintype "passive"))
    )
    (net (code "66") (name "Net-(IC4-15_REXT)") (class "Default")
      (node (ref "IC4") (pin "15") (pinfunction "15_REXT_15") (pintype "bidirectional"))
      (node (ref "R20") (pin "1") (pinfunction "A_1") (pintype "passive"))
    )
    (net (code "67") (name "Net-(IC5-06_OUT1)") (class "Default")
      (node (ref "IC5") (pin "6") (pinfunction "06_OUT1_6") (pintype "output"))
      (node (ref "SW5") (pin "Z-") (pinfunction "Z_Z-") (pintype "bidirectional"))
    )
    (net (code "68") (name "Net-(IC5-07_OUT2)") (class "Default")
      (node (ref "IC5") (pin "7") (pinfunction "07_OUT2_7") (pintype "output"))
      (node (ref "SW5") (pin "P-") (pinfunction "P_P-") (pintype "bidirectional"))
    )
    (net (code "69") (name "Net-(IC5-08_OUT3)") (class "Default")
      (node (ref "IC5") (pin "8") (pinfunction "08_OUT3_8") (pintype "output"))
      (node (ref "SW5") (pin "G2") (pinfunction "G2_G2") (pintype "bidirectional"))
    )
    (net (code "70") (name "Net-(IC5-10_OUT5)") (class "Default")
      (node (ref "IC5") (pin "10") (pinfunction "10_OUT5_10") (pintype "output"))
      (node (ref "SW6") (pin "Z-") (pinfunction "Z_Z-") (pintype "bidirectional"))
    )
    (net (code "71") (name "Net-(IC5-11_OUT6)") (class "Default")
      (node (ref "IC5") (pin "11") (pinfunction "11_OUT6_11") (pintype "output"))
      (node (ref "SW6") (pin "P-") (pinfunction "P_P-") (pintype "bidirectional"))
    )
    (net (code "72") (name "Net-(IC5-12_OUT7)") (class "Default")
      (node (ref "IC5") (pin "12") (pinfunction "12_OUT7_12") (pintype "output"))
      (node (ref "SW6") (pin "G2") (pinfunction "G2_G2") (pintype "bidirectional"))
    )
    (net (code "73") (name "Net-(IC5-14_SDO)") (class "Default")
      (node (ref "IC5") (pin "14") (pinfunction "14_SDO_14") (pintype "output"))
      (node (ref "IC6") (pin "2") (pinfunction "02_SDI_2") (pintype "input"))
      (node (ref "SJ3") (pin "2") (pinfunction "2_2") (pintype "passive"))
      (node (ref "SJ4") (pin "3") (pinfunction "1_3") (pintype "passive"))
    )
    (net (code "74") (name "Net-(IC5-15_REXT)") (class "Default")
      (node (ref "IC5") (pin "15") (pinfunction "15_REXT_15") (pintype "bidirectional"))
      (node (ref "R21") (pin "1") (pinfunction "A_1") (pintype "passive"))
    )
    (net (code "75") (name "Net-(IC6-06_OUT1)") (class "Default")
      (node (ref "IC6") (pin "6") (pinfunction "06_OUT1_6") (pintype "output"))
      (node (ref "SW7") (pin "Z-") (pinfunction "Z_Z-") (pintype "bidirectional"))
    )
    (net (code "76") (name "Net-(IC6-07_OUT2)") (class "Default")
      (node (ref "IC6") (pin "7") (pinfunction "07_OUT2_7") (pintype "output"))
      (node (ref "SW7") (pin "P-") (pinfunction "P_P-") (pintype "bidirectional"))
    )
    (net (code "77") (name "Net-(IC6-08_OUT3)") (class "Default")
      (node (ref "IC6") (pin "8") (pinfunction "08_OUT3_8") (pintype "output"))
      (node (ref "SW7") (pin "G2") (pinfunction "G2_G2") (pintype "bidirectional"))
    )
    (net (code "78") (name "Net-(IC6-10_OUT5)") (class "Default")
      (node (ref "IC6") (pin "10") (pinfunction "10_OUT5_10") (pintype "output"))
      (node (ref "SW8") (pin "Z-") (pinfunction "Z_Z-") (pintype "bidirectional"))
    )
    (net (code "79") (name "Net-(IC6-11_OUT6)") (class "Default")
      (node (ref "IC6") (pin "11") (pinfunction "11_OUT6_11") (pintype "output"))
      (node (ref "SW8") (pin "P-") (pinfunction "P_P-") (pintype "bidirectional"))
    )
    (net (code "80") (name "Net-(IC6-12_OUT7)") (class "Default")
      (node (ref "IC6") (pin "12") (pinfunction "12_OUT7_12") (pintype "output"))
      (node (ref "SW8") (pin "G2") (pinfunction "G2_G2") (pintype "bidirectional"))
    )
    (net (code "81") (name "Net-(IC6-14_SDO)") (class "Default")
      (node (ref "IC6") (pin "14") (pinfunction "14_SDO_14") (pintype "output"))
      (node (ref "IC7") (pin "2") (pinfunction "02_SDI_2") (pintype "input"))
      (node (ref "SJ4") (pin "2") (pinfunction "2_2") (pintype "passive"))
      (node (ref "SJ5") (pin "3") (pinfunction "1_3") (pintype "passive"))
    )
    (net (code "82") (name "Net-(IC6-15_REXT)") (class "Default")
      (node (ref "IC6") (pin "15") (pinfunction "15_REXT_15") (pintype "bidirectional"))
      (node (ref "R22") (pin "1") (pinfunction "A_1") (pintype "passive"))
    )
    (net (code "83") (name "Net-(IC7-06_OUT1)") (class "Default")
      (node (ref "IC7") (pin "6") (pinfunction "06_OUT1_6") (pintype "output"))
      (node (ref "SW9") (pin "Z-") (pinfunction "Z_Z-") (pintype "bidirectional"))
    )
    (net (code "84") (name "Net-(IC7-07_OUT2)") (class "Default")
      (node (ref "IC7") (pin "7") (pinfunction "07_OUT2_7") (pintype "output"))
      (node (ref "SW9") (pin "P-") (pinfunction "P_P-") (pintype "bidirectional"))
    )
    (net (code "85") (name "Net-(IC7-08_OUT3)") (class "Default")
      (node (ref "IC7") (pin "8") (pinfunction "08_OUT3_8") (pintype "output"))
      (node (ref "SW9") (pin "G2") (pinfunction "G2_G2") (pintype "bidirectional"))
    )
    (net (code "86") (name "Net-(IC7-10_OUT5)") (class "Default")
      (node (ref "IC7") (pin "10") (pinfunction "10_OUT5_10") (pintype "output"))
      (node (ref "SW10") (pin "Z-") (pinfunction "Z_Z-") (pintype "bidirectional"))
    )
    (net (code "87") (name "Net-(IC7-11_OUT6)") (class "Default")
      (node (ref "IC7") (pin "11") (pinfunction "11_OUT6_11") (pintype "output"))
      (node (ref "SW10") (pin "P-") (pinfunction "P_P-") (pintype "bidirectional"))
    )
    (net (code "88") (name "Net-(IC7-12_OUT7)") (class "Default")
      (node (ref "IC7") (pin "12") (pinfunction "12_OUT7_12") (pintype "output"))
      (node (ref "SW10") (pin "G2") (pinfunction "G2_G2") (pintype "bidirectional"))
    )
    (net (code "89") (name "Net-(IC7-15_REXT)") (class "Default")
      (node (ref "IC7") (pin "15") (pinfunction "15_REXT_15") (pintype "bidirectional"))
      (node (ref "R13") (pin "1") (pinfunction "A_1") (pintype "passive"))
    )
    (net (code "90") (name "Net-(PIC1-01_~{MCLR})") (class "Default")
      (node (ref "PIC1") (pin "1") (pinfunction "01_~{MCLR}_1") (pintype "input"))
      (node (ref "PROG") (pin "3") (pinfunction "3_3") (pintype "passive"))
      (node (ref "R9") (pin "1") (pinfunction "A_1") (pintype "passive"))
    )
    (net (code "91") (name "Net-(PIC1-06_AN4{slash}C1INB{slash}C2IND{slash}RPB2{slash}SDA2{slash}CTED13{slash}RB2)") (class "Default")
      (node (ref "PIC1") (pin "6") (pinfunction "06_AN4/C1INB/C2IND/RPB2/SDA2/CTED13/RB2_6") (pintype "bidirectional"))
      (node (ref "R17") (pin "1") (pinfunction "A_1") (pintype "passive"))
      (node (ref "R79") (pin "1") (pinfunction "A_1") (pintype "passive"))
    )
    (net (code "92") (name "Net-(PIC1-09_OSC1{slash}CLKI{slash}RPA2{slash}RA2)") (class "Default")
      (node (ref "C1") (pin "1") (pinfunction "1_1") (pintype "passive"))
      (node (ref "PIC1") (pin "9") (pinfunction "09_OSC1/CLKI/RPA2/RA2_9") (pintype "bidirectional"))
      (node (ref "Q1") (pin "P$2") (pinfunction "2_P$2") (pintype "passive"))
    )
    (net (code "93") (name "Net-(PIC1-10_OSC2{slash}CLKO{slash}RPA3{slash}PMA0{slash}RA3)") (class "Default")
      (node (ref "C2") (pin "1") (pinfunction "1_1") (pintype "passive"))
      (node (ref "PIC1") (pin "10") (pinfunction "10_OSC2/CLKO/RPA3/PMA0/RA3_10") (pintype "bidirectional"))
      (node (ref "Q1") (pin "P$1") (pinfunction "1_P$1") (pintype "passive"))
    )
    (net (code "94") (name "Net-(PIC1-12_SOSCO{slash}RPA4{slash}T1CK{slash}CTED9{slash}PMA1{slash}RA4)") (class "Default")
      (node (ref "PIC1") (pin "12") (pinfunction "12_SOSCO/RPA4/T1CK/CTED9/PMA1/RA4_12") (pintype "bidirectional"))
      (node (ref "R28") (pin "2") (pinfunction "E_2") (pintype "passive"))
      (node (ref "R31") (pin "1") (pinfunction "A_1") (pintype "passive"))
    )
    (net (code "95") (name "Net-(PIC1-14_PGED3{slash}RPB5{slash}PMD7{slash}RB5)") (class "Default")
      (node (ref "CN_SYSTEM") (pin "11") (pinfunction "11_11") (pintype "passive"))
      (node (ref "CN_SYSTEM") (pin "12") (pinfunction "12_12") (pintype "passive"))
      (node (ref "PIC1") (pin "14") (pinfunction "14_PGED3/RPB5/PMD7/RB5_14") (pintype "bidirectional"))
      (node (ref "PROG") (pin "4") (pinfunction "4_4") (pintype "passive"))
    )
    (net (code "96") (name "Net-(PIC1-15_PGEC3{slash}RPB6{slash}PMD6{slash}RB6)") (class "Default")
      (node (ref "PIC1") (pin "15") (pinfunction "15_PGEC3/RPB6/PMD6/RB6_15") (pintype "bidirectional"))
      (node (ref "PROG") (pin "5") (pinfunction "5_5") (pintype "passive"))
      (node (ref "R27") (pin "2") (pinfunction "E_2") (pintype "passive"))
      (node (ref "SW1") (pin "G1") (pinfunction "G1_G1") (pintype "bidirectional"))
      (node (ref "SW10") (pin "G1") (pinfunction "G1_G1") (pintype "bidirectional"))
      (node (ref "SW2") (pin "G1") (pinfunction "G1_G1") (pintype "bidirectional"))
      (node (ref "SW3") (pin "G1") (pinfunction "G1_G1") (pintype "bidirectional"))
      (node (ref "SW4") (pin "G1") (pinfunction "G1_G1") (pintype "bidirectional"))
      (node (ref "SW5") (pin "G1") (pinfunction "G1_G1") (pintype "bidirectional"))
      (node (ref "SW6") (pin "G1") (pinfunction "G1_G1") (pintype "bidirectional"))
      (node (ref "SW7") (pin "G1") (pinfunction "G1_G1") (pintype "bidirectional"))
      (node (ref "SW8") (pin "G1") (pinfunction "G1_G1") (pintype "bidirectional"))
      (node (ref "SW9") (pin "G1") (pinfunction "G1_G1") (pintype "bidirectional"))
    )
    (net (code "97") (name "Net-(PIC1-16_TDI{slash}RPB7{slash}CTED3{slash}PMD5{slash}INT0{slash}RB7)") (class "Default")
      (node (ref "CN_SYSTEM") (pin "13") (pinfunction "13_13") (pintype "passive"))
      (node (ref "CN_SYSTEM") (pin "14") (pinfunction "14_14") (pintype "passive"))
      (node (ref "PIC1") (pin "16") (pinfunction "16_TDI/RPB7/CTED3/PMD5/INT0/RB7_16") (pintype "bidirectional"))
    )
    (net (code "98") (name "Net-(PIC1-17_TCK{slash}RPB8{slash}SCL1{slash}CTED10{slash}PMD4{slash}RB8)") (class "Default")
      (node (ref "PIC1") (pin "17") (pinfunction "17_TCK/RPB8/SCL1/CTED10/PMD4/RB8_17") (pintype "bidirectional"))
      (node (ref "R29") (pin "1") (pinfunction "A_1") (pintype "passive"))
    )
    (net (code "99") (name "Net-(PIC1-18_TDO{slash}RPB9{slash}SDA1{slash}CTED4{slash}PMD3{slash}RB9)") (class "Default")
      (node (ref "PIC1") (pin "18") (pinfunction "18_TDO/RPB9/SDA1/CTED4/PMD3/RB9_18") (pintype "bidirectional"))
      (node (ref "R30") (pin "1") (pinfunction "A_1") (pintype "passive"))
    )
    (net (code "100") (name "Net-(PIC1-20_VCAP)") (class "Default")
      (node (ref "C6") (pin "1") (pinfunction "1_1") (pintype "passive"))
      (node (ref "PIC1") (pin "20") (pinfunction "20_VCAP_20") (pintype "power_in"))
    )
    (net (code "101") (name "Net-(PIC1-24_AN11{slash}RPB13{slash}CTPLS{slash}PMRD{slash}RB13)") (class "Default")
      (node (ref "CN_SYSTEM") (pin "10") (pinfunction "10_10") (pintype "passive"))
      (node (ref "CN_SYSTEM") (pin "9") (pinfunction "9_9") (pintype "passive"))
      (node (ref "PIC1") (pin "24") (pinfunction "24_AN11/RPB13/CTPLS/PMRD/RB13_24") (pintype "bidirectional"))
    )
    (net (code "102") (name "Net-(PIC1-25_CVREFOUT{slash}AN10{slash}C3INB{slash}RPB14{slash}SCK1{slash}CTED5{slash}PMWR{slash}RB14)") (class "Default")
      (node (ref "CN_SYSTEM") (pin "7") (pinfunction "7_7") (pintype "passive"))
      (node (ref "CN_SYSTEM") (pin "8") (pinfunction "8_8") (pintype "passive"))
      (node (ref "PIC1") (pin "25") (pinfunction "25_CVREFOUT/AN10/C3INB/RPB14/SCK1/CTED5/PMWR/RB14_25") (pintype "bidirectional"))
    )
    (net (code "103") (name "Net-(Q2-B)") (class "Default")
      (node (ref "Q2") (pin "1") (pinfunction "B_1") (pintype "passive"))
      (node (ref "R17") (pin "2") (pinfunction "E_2") (pintype "passive"))
    )
    (net (code "104") (name "Net-(Q2-C)") (class "Default")
      (node (ref "Q2") (pin "3") (pinfunction "C_3") (pintype "passive"))
      (node (ref "R26") (pin "2") (pinfunction "E_2") (pintype "passive"))
    )
    (net (code "105") (name "Net-(R1-E)") (class "Default")
      (node (ref "R1") (pin "2") (pinfunction "E_2") (pintype "passive"))
      (node (ref "R11") (pin "2") (pinfunction "E_2") (pintype "passive"))
      (node (ref "R12") (pin "1") (pinfunction "A_1") (pintype "passive"))
      (node (ref "R2") (pin "1") (pinfunction "A_1") (pintype "passive"))
      (node (ref "R26") (pin "1") (pinfunction "A_1") (pintype "passive"))
      (node (ref "R3") (pin "2") (pinfunction "E_2") (pintype "passive"))
      (node (ref "R4") (pin "1") (pinfunction "A_1") (pintype "passive"))
      (node (ref "R5") (pin "2") (pinfunction "E_2") (pintype "passive"))
      (node (ref "R6") (pin "1") (pinfunction "A_1") (pintype "passive"))
      (node (ref "R7") (pin "2") (pinfunction "E_2") (pintype "passive"))
      (node (ref "R8") (pin "1") (pinfunction "A_1") (pintype "passive"))
    )
    (net (code "106") (name "Net-(R10-E)") (class "Default")
      (node (ref "C20") (pin "P+") (pinfunction "P+_P+") (pintype "passive"))
      (node (ref "R10") (pin "2") (pinfunction "E_2") (pintype "passive"))
      (node (ref "R13") (pin "2") (pinfunction "E_2") (pintype "passive"))
      (node (ref "R18") (pin "2") (pinfunction "E_2") (pintype "passive"))
      (node (ref "R19") (pin "2") (pinfunction "E_2") (pintype "passive"))
      (node (ref "R20") (pin "2") (pinfunction "E_2") (pintype "passive"))
      (node (ref "R21") (pin "2") (pinfunction "E_2") (pintype "passive"))
      (node (ref "R22") (pin "2") (pinfunction "E_2") (pintype "passive"))
      (node (ref "R31") (pin "2") (pinfunction "E_2") (pintype "passive"))
      (node (ref "R32") (pin "1") (pinfunction "A_1") (pintype "passive"))
    )
    (net (code "107") (name "Net-(R51-A)") (class "Default")
      (node (ref "C28") (pin "2") (pinfunction "2_2") (pintype "passive"))
      (node (ref "R51") (pin "1") (pinfunction "A_1") (pintype "passive"))
    )
    (net (code "108") (name "unconnected-(IC1-11_OUT6-Pad11)") (class "Default")
      (node (ref "IC1") (pin "11") (pinfunction "11_OUT6_11") (pintype "output"))
    )
    (net (code "109") (name "unconnected-(IC1-12_OUT7-Pad12)") (class "Default")
      (node (ref "IC1") (pin "12") (pinfunction "12_OUT7_12") (pintype "output"))
    )
    (net (code "110") (name "unconnected-(IC2-11_OUT6-Pad11)") (class "Default")
      (node (ref "IC2") (pin "11") (pinfunction "11_OUT6_11") (pintype "output"))
    )
    (net (code "111") (name "unconnected-(IC2-12_OUT7-Pad12)") (class "Default")
      (node (ref "IC2") (pin "12") (pinfunction "12_OUT7_12") (pintype "output"))
    )
    (net (code "112") (name "unconnected-(PIC1-02_VREF+{slash}VREF+{slash}AN0{slash}C3INC{slash}RPA0{slash}CTED1{slash}RA0-Pad2)") (class "Default")
      (node (ref "PIC1") (pin "2") (pinfunction "02_VREF+/VREF+/AN0/C3INC/RPA0/CTED1/RA0_2") (pintype "bidirectional"))
    )
    (net (code "113") (name "unconnected-(PIC1-03_VREF-{slash}CVREF-{slash}AN1{slash}RPA1{slash}CTED2{slash}RA1-Pad3)") (class "Default")
      (node (ref "PIC1") (pin "3") (pinfunction "03_VREF-/CVREF-/AN1/RPA1/CTED2/RA1_3") (pintype "bidirectional"))
    )
    (net (code "114") (name "unconnected-(PIC1-04_PGED1{slash}AN2{slash}C1IND{slash}C2INB{slash}C3IND{slash}RPB0{slash}RB0-Pad4)") (class "Default")
      (node (ref "PIC1") (pin "4") (pinfunction "04_PGED1/AN2/C1IND/C2INB/C3IND/RPB0/RB0_4") (pintype "bidirectional"))
    )
    (net (code "115") (name "unconnected-(PIC1-05_PGEC1{slash}AN3{slash}C1INC{slash}C2INA{slash}RPB1{slash}CTED12{slash}RB1-Pad5)") (class "Default")
      (node (ref "PIC1") (pin "5") (pinfunction "05_PGEC1/AN3/C1INC/C2INA/RPB1/CTED12/RB1_5") (pintype "bidirectional"))
    )
    (net (code "116") (name "unconnected-(PIC1-07_AN5{slash}C1INA{slash}C2INC{slash}RTCC{slash}RPB3{slash}SCL2{slash}RB3-Pad7)") (class "Default")
      (node (ref "PIC1") (pin "7") (pinfunction "07_AN5/C1INA/C2INC/RTCC/RPB3/SCL2/RB3_7") (pintype "bidirectional"))
    )
    (net (code "117") (name "unconnected-(PIC1-11_SOSCI{slash}RPB4{slash}RB4-Pad11)") (class "Default")
      (node (ref "PIC1") (pin "11") (pinfunction "11_SOSCI/RPB4/RB4_11") (pintype "bidirectional"))
    )
  )
)
